# Sheet1.net
KiCad netlist of a schematic drawn in Altium Designer
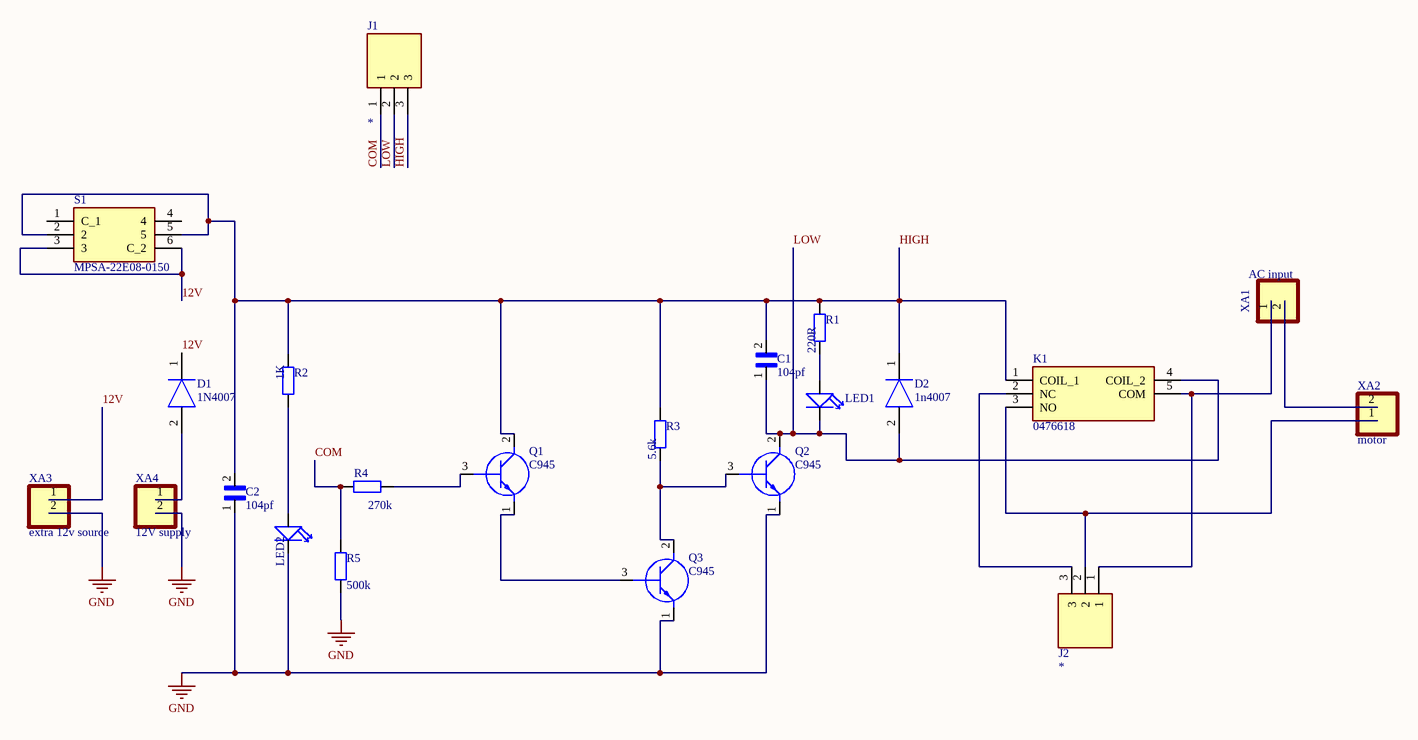
[diagram p0: Sheet1.SchDoc]

(export (version "E")
  (design (tool "Eeschema 10.0.6"))
  (components
    (comp (ref "C1")
      (value "104pf")
      (footprint "CAP_DE21XSA100KN3AY02F")
      (fields (field (name "MP") "DE21XSA100KN3AY02F"))
      (libsource (lib "nonpolar capacitor round 3D") (part "DE21XSA100KN3AY02F"))
    )
    (comp (ref "C2")
      (value "104pf")
      (footprint "CAP_DE21XSA100KN3AY02F")
      (fields (field (name "MP") "DE21XSA100KN3AY02F"))
      (libsource (lib "nonpolar capacitor round 3D") (part "DE21XSA100KN3AY02F"))
    )
    (comp (ref "D1")
      (value "1N4007")
      (footprint "DIOAD1138W56L406D183")
      (description "Diode")
      (fields (field (name "MANUFACTURER_PART_NUMBER") "1N4678 (DO35)"))
      (libsource (lib "diode with 3d model") (part "1N4678__DO35_"))
    )
    (comp (ref "D2")
      (value "1n4007")
      (footprint "DIOAD1138W56L406D183")
      (description "Diode")
      (fields (field (name "MANUFACTURER_PART_NUMBER") "1N4678 (DO35)"))
      (libsource (lib "diode with 3d model") (part "1N4678__DO35_"))
    )
    (comp (ref "J1")
      (value "1776118-3")
      (footprint "TE_1776118-3")
      (description "Conn Terminal Block F 3 POS 5mm Solder ST Thru-Hole Package")
      (fields (field (name "MF") "TE Connectivity") (field (name "COMMENT_1") "*"))
      (libsource (lib "") (part "1776118-3_1"))
    )
    (comp (ref "J2")
      (value "1776118-3")
      (footprint "TE_1776118-3")
      (description "Conn Terminal Block F 3 POS 5mm Solder ST Thru-Hole Package")
      (fields (field (name "MF") "TE Connectivity") (field (name "COMMENT_1") "*"))
      (libsource (lib "3pin connector") (part "1776118-3"))
    )
    (comp (ref "K1")
      (value "0476618")
      (footprint "SamacSys:0476618")
      (description "Relay or Contactor")
      (libsource (lib "relay 5 pin") (part "0476618"))
    )
    (comp (ref "LED1")
      (value "~")
      (footprint "LED2-2.54-D10MM")
      (description "DIP LED Green-Vaporous Green-10mm")
      (fields (field (name "MF") "Chengguangxing") (field (name "MP") "G1004DC"))
      (libsource (lib "LED 3D") (part "DIP-LED-GREEN-VAPOROUS-GREEN-10MM(2P-D10MM)"))
    )
    (comp (ref "LED2")
      (value "~")
      (footprint "LED2-2.54-D10MM")
      (description "DIP LED Green-Vaporous Green-10mm")
      (fields (field (name "MF") "Chengguangxing") (field (name "MP") "G1004DC"))
      (libsource (lib "LED 3D") (part "DIP-LED-GREEN-VAPOROUS-GREEN-10MM(2P-D10MM)"))
    )
    (comp (ref "Q1")
      (value "C945")
      (footprint "TO229P300X760X1364-3P")
      (description "Transistor BJT NPN")
      (fields
        (field (name "MANUFACTURER_PART_NUMBER") "BD139G")
        (field (name "MOUSER PART NUMBER") "863-BD139G")
      )
      (libsource (lib "BD139 NPN transistor") (part "BD139G"))
    )
    (comp (ref "Q2")
      (value "C945")
      (footprint "TO229P300X760X1364-3P")
      (description "Transistor BJT NPN")
      (fields
        (field (name "MANUFACTURER_PART_NUMBER") "BD139G")
        (field (name "MOUSER PART NUMBER") "863-BD139G")
      )
      (libsource (lib "BD139 NPN transistor") (part "BD139G"))
    )
    (comp (ref "Q3")
      (value "C945")
      (footprint "TO229P300X760X1364-3P")
      (description "Transistor BJT NPN")
      (fields
        (field (name "MANUFACTURER_PART_NUMBER") "BD139G")
        (field (name "MOUSER PART NUMBER") "863-BD139G")
      )
      (libsource (lib "BD139 NPN transistor") (part "BD139G"))
    )
    (comp (ref "R1")
      (value "220R")
      (footprint "AXIAL-0.4")
      (description "Resistor")
      (fields (field (name "PUBLISHER") "Altium Limited"))
      (libsource (lib "Miscellaneous Devices") (part "Res2"))
    )
    (comp (ref "R2")
      (value "1K")
      (footprint "AXIAL-0.4")
      (description "Resistor")
      (fields (field (name "PUBLISHER") "Altium Limited"))
      (libsource (lib "Miscellaneous Devices") (part "Res2"))
    )
    (comp (ref "R3")
      (value "5.6k")
      (footprint "AXIAL-0.4")
      (description "Resistor")
      (fields (field (name "PUBLISHER") "Altium Limited"))
      (libsource (lib "Miscellaneous Devices") (part "Res2"))
    )
    (comp (ref "R4")
      (value "270k")
      (footprint "AXIAL-0.4")
      (description "Resistor")
      (fields (field (name "PUBLISHER") "Altium Limited"))
      (libsource (lib "") (part "Res2_1"))
    )
    (comp (ref "R5")
      (value "500k")
      (footprint "AXIAL-0.4")
      (description "Resistor")
      (fields (field (name "PUBLISHER") "Altium Limited"))
      (libsource (lib "Miscellaneous Devices") (part "Res2"))
    )
    (comp (ref "S1")
      (value "MPSA-22E08-0150")
      (footprint "SamacSys:MPSA22E080150")
      (description "Switch")
      (libsource (lib "6pin push button") (part "MPSA-22E08-0150"))
    )
    (comp (ref "XA1")
      (value "AC input")
      (footprint "PHOENIX_MKDS1/2-3.81")
      (description "2 Position Wire to Board Terminal Block Horizontal with Board 0.150 _3.81mm_ Through Hole")
      (fields (field (name "MF") "Phoenix Contact") (field (name "MP") "MKDS 1/ 2-3.81"))
      (libsource (lib "") (part "MKDS1/2-3.81_1"))
    )
    (comp (ref "XA2")
      (value "motor")
      (footprint "PHOENIX_MKDS1/2-3.81")
      (description "2 Position Wire to Board Terminal Block Horizontal with Board 0.150 _3.81mm_ Through Hole")
      (fields (field (name "MF") "Phoenix Contact") (field (name "MP") "MKDS 1/ 2-3.81"))
      (libsource (lib "") (part "MKDS1/2-3.81_1"))
    )
    (comp (ref "XA3")
      (value "extra 12v source")
      (footprint "PHOENIX_MKDS1/2-3.81")
      (description "2 Position Wire to Board Terminal Block Horizontal with Board 0.150 _3.81mm_ Through Hole")
      (fields (field (name "MF") "Phoenix Contact") (field (name "MP") "MKDS 1/ 2-3.81"))
      (libsource (lib "connector 2 pin 3D1") (part "MKDS1/2-3.81"))
    )
    (comp (ref "XA4")
      (value "12V supply")
      (footprint "PHOENIX_MKDS1/2-3.81")
      (description "2 Position Wire to Board Terminal Block Horizontal with Board 0.150 _3.81mm_ Through Hole")
      (fields (field (name "MF") "Phoenix Contact") (field (name "MP") "MKDS 1/ 2-3.81"))
      (libsource (lib "connector 2 pin 3D1") (part "MKDS1/2-3.81"))
    )
  )
  (nets
    (net (code "1") (name "/12V") (class "Default")
      (node (ref "D1") (pin "1") (pinfunction "K_1") (pintype "passive"))
      (node (ref "S1") (pin "3") (pinfunction "3_3") (pintype "passive"))
      (node (ref "S1") (pin "6") (pinfunction "C_2_6") (pintype "passive"))
      (node (ref "XA3") (pin "1") (pinfunction "1_1") (pintype "passive"))
    )
    (net (code "2") (name "/COM") (class "Default")
      (node (ref "J1") (pin "1") (pinfunction "1_1") (pintype "passive"))
      (node (ref "R4") (pin "1") (pinfunction "1_1") (pintype "passive"))
      (node (ref "R5") (pin "2") (pinfunction "2_2") (pintype "passive"))
    )
    (net (code "3") (name "/HIGH") (class "Default")
      (node (ref "C1") (pin "2") (pinfunction "2_2") (pintype "passive"))
      (node (ref "C2") (pin "2") (pinfunction "2_2") (pintype "passive"))
      (node (ref "D2") (pin "1") (pinfunction "K_1") (pintype "passive"))
      (node (ref "J1") (pin "3") (pinfunction "3_3") (pintype "passive"))
      (node (ref "K1") (pin "1") (pinfunction "COIL_1_1") (pintype "passive"))
      (node (ref "Q1") (pin "2") (pinfunction "C_2") (pintype "passive"))
      (node (ref "R1") (pin "2") (pinfunction "2_2") (pintype "passive"))
      (node (ref "R2") (pin "2") (pinfunction "2_2") (pintype "passive"))
      (node (ref "R3") (pin "2") (pinfunction "2_2") (pintype "passive"))
      (node (ref "S1") (pin "2") (pinfunction "2_2") (pintype "passive"))
      (node (ref "S1") (pin "5") (pinfunction "5_5") (pintype "passive"))
    )
    (net (code "4") (name "/LOW") (class "Default")
      (node (ref "C1") (pin "1") (pinfunction "1_1") (pintype "passive"))
      (node (ref "D2") (pin "2") (pinfunction "A_2") (pintype "passive"))
      (node (ref "J1") (pin "2") (pinfunction "2_2") (pintype "passive"))
      (node (ref "K1") (pin "4") (pinfunction "COIL_2_4") (pintype "passive"))
      (node (ref "LED1") (pin "NEG") (pinfunction "NEG_NEG") (pintype "passive"))
      (node (ref "Q2") (pin "2") (pinfunction "C_2") (pintype "passive"))
    )
    (net (code "5") (name "GND") (class "Default")
      (node (ref "C2") (pin "1") (pinfunction "1_1") (pintype "passive"))
      (node (ref "LED2") (pin "NEG") (pinfunction "NEG_NEG") (pintype "passive"))
      (node (ref "Q2") (pin "1") (pinfunction "E_1") (pintype "passive"))
      (node (ref "Q3") (pin "1") (pinfunction "E_1") (pintype "passive"))
      (node (ref "R5") (pin "1") (pinfunction "1_1") (pintype "passive"))
      (node (ref "XA3") (pin "2") (pinfunction "2_2") (pintype "passive"))
      (node (ref "XA4") (pin "2") (pinfunction "2_2") (pintype "passive"))
    )
    (net (code "6") (name "Net-(D1-A)") (class "Default")
      (node (ref "D1") (pin "2") (pinfunction "A_2") (pintype "passive"))
      (node (ref "XA4") (pin "1") (pinfunction "1_1") (pintype "passive"))
    )
    (net (code "7") (name "Net-(K1-COM)") (class "Default")
      (node (ref "J2") (pin "1") (pinfunction "1_1") (pintype "passive"))
      (node (ref "K1") (pin "5") (pinfunction "COM_5") (pintype "passive"))
      (node (ref "XA1") (pin "1") (pinfunction "1_1") (pintype "passive"))
    )
    (net (code "8") (name "Net-(K1-NC)") (class "Default")
      (node (ref "J2") (pin "3") (pinfunction "3_3") (pintype "passive"))
      (node (ref "K1") (pin "2") (pinfunction "NC_2") (pintype "passive"))
    )
    (net (code "9") (name "Net-(K1-NO)") (class "Default")
      (node (ref "J2") (pin "2") (pinfunction "2_2") (pintype "passive"))
      (node (ref "K1") (pin "3") (pinfunction "NO_3") (pintype "passive"))
      (node (ref "XA2") (pin "1") (pinfunction "1_1") (pintype "passive"))
    )
    (net (code "10") (name "Net-(LED1-PadPOS)") (class "Default")
      (node (ref "LED1") (pin "POS") (pinfunction "POS_POS") (pintype "passive"))
      (node (ref "R1") (pin "1") (pinfunction "1_1") (pintype "passive"))
    )
    (net (code "11") (name "Net-(LED2-PadPOS)") (class "Default")
      (node (ref "LED2") (pin "POS") (pinfunction "POS_POS") (pintype "passive"))
      (node (ref "R2") (pin "1") (pinfunction "1_1") (pintype "passive"))
    )
    (net (code "12") (name "Net-(Q1-B)") (class "Default")
      (node (ref "Q1") (pin "3") (pinfunction "B_3") (pintype "passive"))
      (node (ref "R4") (pin "2") (pinfunction "2_2") (pintype "passive"))
    )
    (net (code "13") (name "Net-(Q1-E)") (class "Default")
      (node (ref "Q1") (pin "1") (pinfunction "E_1") (pintype "passive"))
      (node (ref "Q3") (pin "3") (pinfunction "B_3") (pintype "passive"))
    )
    (net (code "14") (name "Net-(Q2-B)") (class "Default")
      (node (ref "Q2") (pin "3") (pinfunction "B_3") (pintype "passive"))
      (node (ref "Q3") (pin "2") (pinfunction "C_2") (pintype "passive"))
      (node (ref "R3") (pin "1") (pinfunction "1_1") (pintype "passive"))
    )
    (net (code "15") (name "Net-(XA1-Pad2)") (class "Default")
      (node (ref "XA1") (pin "2") (pinfunction "2_2") (pintype "passive"))
      (node (ref "XA2") (pin "2") (pinfunction "2_2") (pintype "passive"))
    )
    (net (code "16") (name "unconnected-(S1-C_1-Pad1)") (class "Default")
      (node (ref "S1") (pin "1") (pinfunction "C_1_1") (pintype "passive"))
    )
    (net (code "17") (name "unconnected-(S1-Pad4)") (class "Default")
      (node (ref "S1") (pin "4") (pinfunction "4_4") (pintype "passive"))
    )
  )
)
